# sapflux_base_v2_2.net
KiCad netlist of a schematic drawn in EAGLE
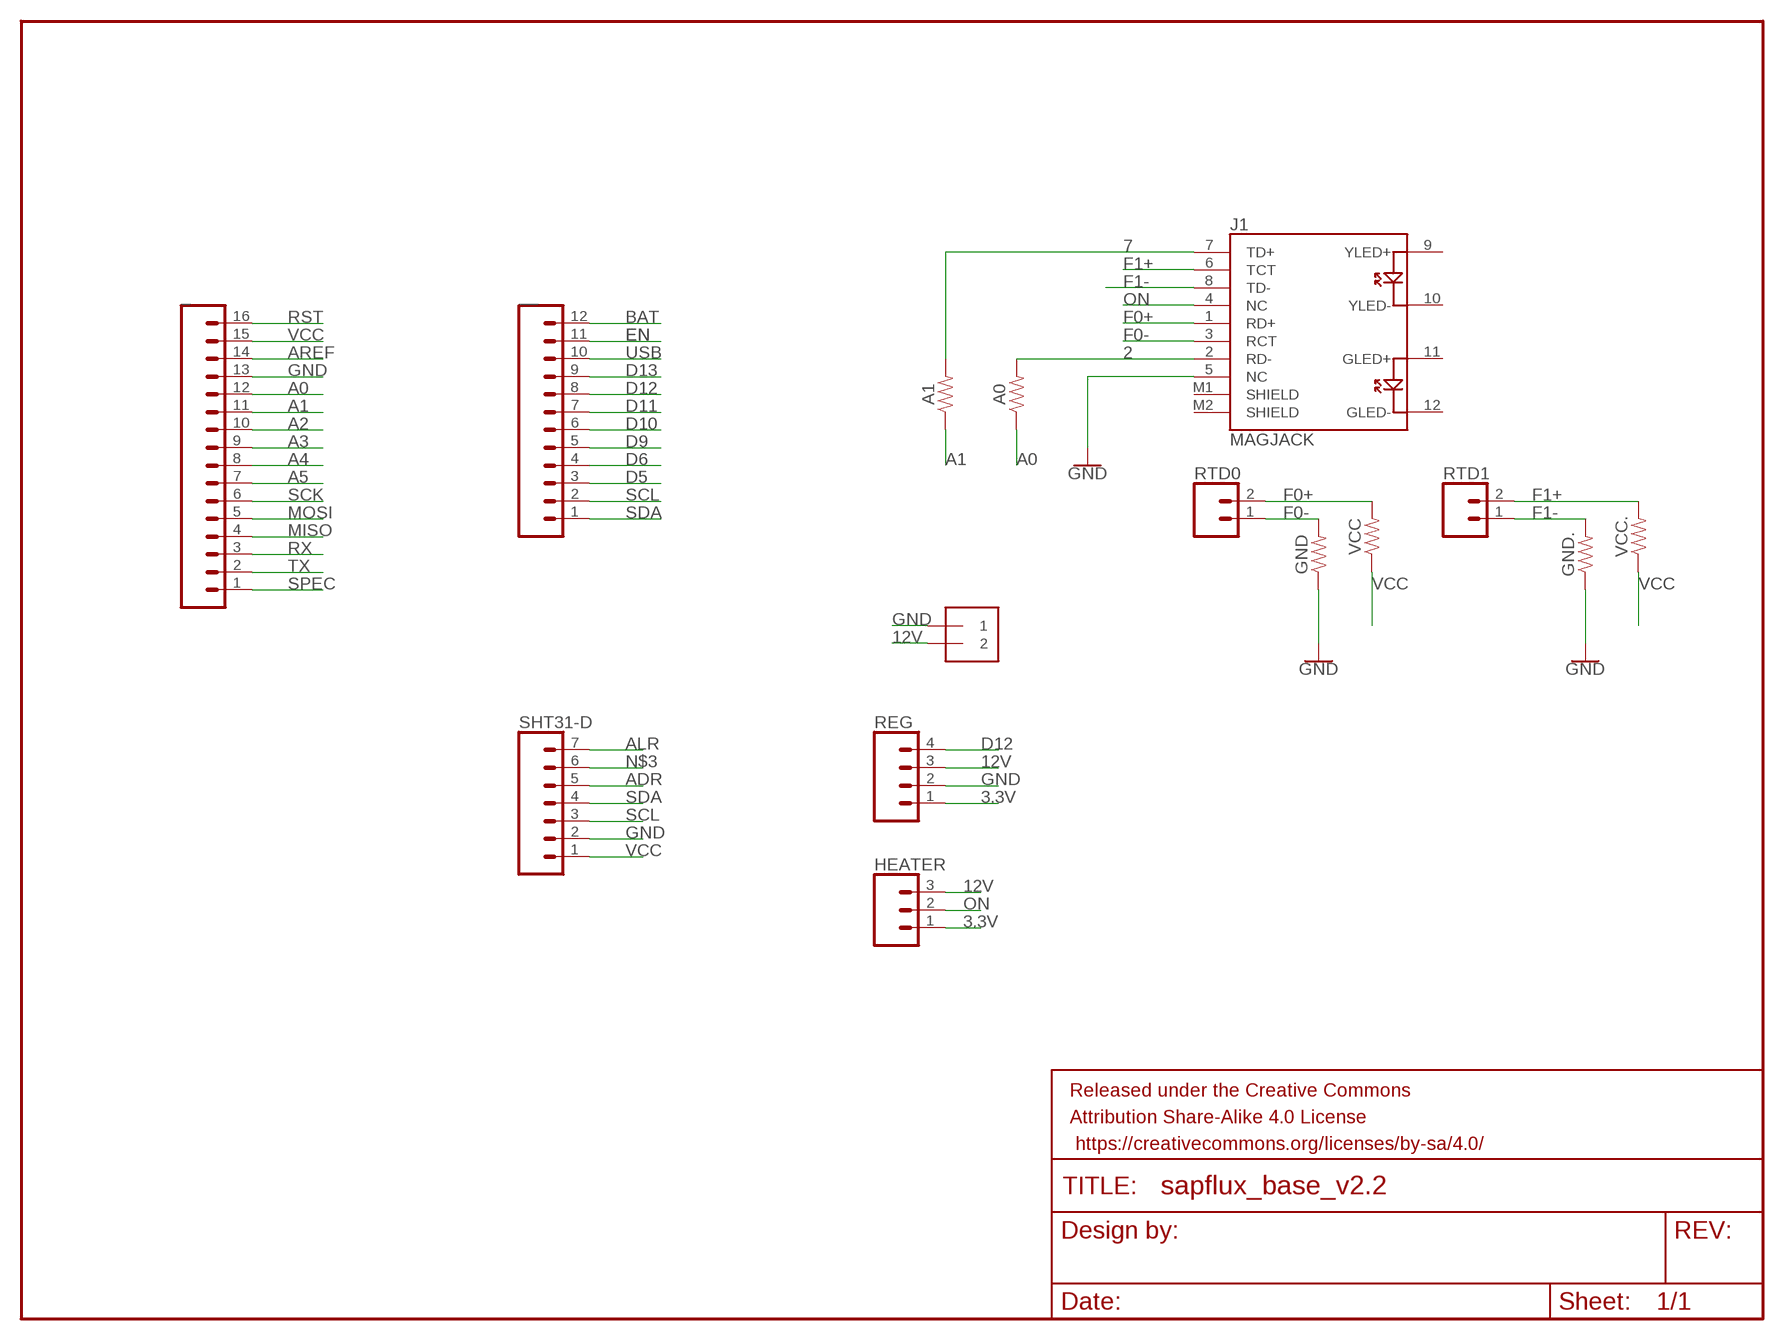
[diagram p0: schematic, sheet 1]

(export (version "E")
  (design (tool "Eeschema 10.0.6"))
  (components
    (comp (ref ".")
      (value "1X2-3.5MM")
      (footprint "eagle-import:1X2-3.5MM")
      (libsource (lib "eagle-import") (part "1X2-3.5MM"))
    )
    (comp (ref "A0")
      (value "1.8MOHM")
      (footprint "eagle-import:0603")
      (libsource (lib "eagle-import") (part "1.8MOHM"))
    )
    (comp (ref "A1")
      (value "1.8MOHM")
      (footprint "eagle-import:0603")
      (libsource (lib "eagle-import") (part "1.8MOHM"))
    )
    (comp (ref "FRAME1")
      (value "FRAME-LETTER")
      (footprint "eagle-import:CREATIVE_COMMONS")
      (libsource (lib "eagle-import") (part "FRAME-LETTER"))
    )
    (comp (ref "GND")
      (value "1.8MOHM")
      (footprint "eagle-import:0603")
      (libsource (lib "eagle-import") (part "1.8MOHM"))
    )
    (comp (ref "GND.")
      (value "1.8MOHM")
      (footprint "eagle-import:0603")
      (libsource (lib "eagle-import") (part "1.8MOHM"))
    )
    (comp (ref "HEATER")
      (value "CONN_03")
      (footprint "eagle-import:1X03")
      (libsource (lib "eagle-import") (part "CONN_03"))
    )
    (comp (ref "J1")
      (value "MAGJACK")
      (footprint "eagle-import:MAGJACK")
      (libsource (lib "eagle-import") (part "MAGJACK"))
    )
    (comp (ref "REG")
      (value "CONN_04")
      (footprint "eagle-import:1X04")
      (libsource (lib "eagle-import") (part "CONN_04"))
    )
    (comp (ref "RTD0")
      (value "CONN_02")
      (footprint "eagle-import:1X02")
      (libsource (lib "eagle-import") (part "CONN_02"))
    )
    (comp (ref "RTD1")
      (value "CONN_02")
      (footprint "eagle-import:1X02")
      (libsource (lib "eagle-import") (part "CONN_02"))
    )
    (comp (ref "SHT31-D")
      (value "CONN_07")
      (footprint "eagle-import:1X07")
      (libsource (lib "eagle-import") (part "CONN_07"))
    )
    (comp (ref "VCC")
      (value "1.8MOHM")
      (footprint "eagle-import:0603")
      (libsource (lib "eagle-import") (part "1.8MOHM"))
    )
    (comp (ref "VCC.")
      (value "1.8MOHM")
      (footprint "eagle-import:0603")
      (libsource (lib "eagle-import") (part "1.8MOHM"))
    )
    (comp (ref "_")
      (value "CONN_16")
      (footprint "eagle-import:1X16")
      (libsource (lib "eagle-import") (part "CONN_16"))
    )
    (comp (ref "__")
      (value "CONN_12")
      (footprint "eagle-import:1X12")
      (libsource (lib "eagle-import") (part "CONN_12"))
    )
  )
  (nets
    (net (code "1") (name "/2") (class "Default")
      (node (ref "A0") (pin "2") (pinfunction "2_2") (pintype "passive"))
      (node (ref "J1") (pin "2") (pinfunction "RD-_2") (pintype "bidirectional"))
    )
    (net (code "2") (name "/3.3V") (class "Default")
      (node (ref "HEATER") (pin "1") (pinfunction "1_1") (pintype "passive"))
      (node (ref "REG") (pin "1") (pinfunction "1_1") (pintype "passive"))
    )
    (net (code "3") (name "/7") (class "Default")
      (node (ref "A1") (pin "2") (pinfunction "2_2") (pintype "passive"))
      (node (ref "J1") (pin "7") (pinfunction "TD+_7") (pintype "bidirectional"))
    )
    (net (code "4") (name "/12V") (class "Default")
      (node (ref ".") (pin "2") (pinfunction "2_2") (pintype "passive"))
      (node (ref "HEATER") (pin "3") (pinfunction "3_3") (pintype "passive"))
      (node (ref "REG") (pin "3") (pinfunction "3_3") (pintype "passive"))
    )
    (net (code "5") (name "/A0") (class "Default")
      (node (ref "A0") (pin "1") (pinfunction "1_1") (pintype "passive"))
      (node (ref "_") (pin "12") (pinfunction "12_12") (pintype "passive"))
    )
    (net (code "6") (name "/A1") (class "Default")
      (node (ref "A1") (pin "1") (pinfunction "1_1") (pintype "passive"))
      (node (ref "_") (pin "11") (pinfunction "11_11") (pintype "passive"))
    )
    (net (code "7") (name "/A2") (class "Default")
      (node (ref "_") (pin "10") (pinfunction "10_10") (pintype "passive"))
    )
    (net (code "8") (name "/A3") (class "Default")
      (node (ref "_") (pin "9") (pinfunction "9_9") (pintype "passive"))
    )
    (net (code "9") (name "/A4") (class "Default")
      (node (ref "_") (pin "8") (pinfunction "8_8") (pintype "passive"))
    )
    (net (code "10") (name "/A5") (class "Default")
      (node (ref "_") (pin "7") (pinfunction "7_7") (pintype "passive"))
    )
    (net (code "11") (name "/ADR") (class "Default")
      (node (ref "SHT31-D") (pin "5") (pinfunction "5_5") (pintype "passive"))
    )
    (net (code "12") (name "/ALR") (class "Default")
      (node (ref "SHT31-D") (pin "7") (pinfunction "7_7") (pintype "passive"))
    )
    (net (code "13") (name "/AREF") (class "Default")
      (node (ref "_") (pin "14") (pinfunction "14_14") (pintype "passive"))
    )
    (net (code "14") (name "/BAT") (class "Default")
      (node (ref "__") (pin "12") (pinfunction "12_12") (pintype "passive"))
    )
    (net (code "15") (name "/D5") (class "Default")
      (node (ref "__") (pin "3") (pinfunction "3_3") (pintype "passive"))
    )
    (net (code "16") (name "/D6") (class "Default")
      (node (ref "__") (pin "4") (pinfunction "4_4") (pintype "passive"))
    )
    (net (code "17") (name "/D9") (class "Default")
      (node (ref "__") (pin "5") (pinfunction "5_5") (pintype "passive"))
    )
    (net (code "18") (name "/D10") (class "Default")
      (node (ref "__") (pin "6") (pinfunction "6_6") (pintype "passive"))
    )
    (net (code "19") (name "/D11") (class "Default")
      (node (ref "__") (pin "7") (pinfunction "7_7") (pintype "passive"))
    )
    (net (code "20") (name "/D12") (class "Default")
      (node (ref "REG") (pin "4") (pinfunction "4_4") (pintype "passive"))
      (node (ref "__") (pin "8") (pinfunction "8_8") (pintype "passive"))
    )
    (net (code "21") (name "/D13") (class "Default")
      (node (ref "__") (pin "9") (pinfunction "9_9") (pintype "passive"))
    )
    (net (code "22") (name "/EN") (class "Default")
      (node (ref "__") (pin "11") (pinfunction "11_11") (pintype "passive"))
    )
    (net (code "23") (name "/F0+") (class "Default")
      (node (ref "J1") (pin "1") (pinfunction "RD+_1") (pintype "bidirectional"))
      (node (ref "RTD0") (pin "2") (pinfunction "2_2") (pintype "passive"))
      (node (ref "VCC") (pin "2") (pinfunction "2_2") (pintype "passive"))
    )
    (net (code "24") (name "/F0-") (class "Default")
      (node (ref "GND") (pin "2") (pinfunction "2_2") (pintype "passive"))
      (node (ref "J1") (pin "3") (pinfunction "RCT_3") (pintype "bidirectional"))
      (node (ref "RTD0") (pin "1") (pinfunction "1_1") (pintype "passive"))
    )
    (net (code "25") (name "/F1+") (class "Default")
      (node (ref "J1") (pin "6") (pinfunction "TCT_6") (pintype "bidirectional"))
      (node (ref "RTD1") (pin "2") (pinfunction "2_2") (pintype "passive"))
      (node (ref "VCC.") (pin "2") (pinfunction "2_2") (pintype "passive"))
    )
    (net (code "26") (name "/F1-") (class "Default")
      (node (ref "GND.") (pin "2") (pinfunction "2_2") (pintype "passive"))
      (node (ref "J1") (pin "8") (pinfunction "TD-_8") (pintype "bidirectional"))
      (node (ref "RTD1") (pin "1") (pinfunction "1_1") (pintype "passive"))
    )
    (net (code "27") (name "/MISO") (class "Default")
      (node (ref "_") (pin "4") (pinfunction "4_4") (pintype "passive"))
    )
    (net (code "28") (name "/MOSI") (class "Default")
      (node (ref "_") (pin "5") (pinfunction "5_5") (pintype "passive"))
    )
    (net (code "29") (name "/N$3") (class "Default")
      (node (ref "SHT31-D") (pin "6") (pinfunction "6_6") (pintype "passive"))
    )
    (net (code "30") (name "/ON") (class "Default")
      (node (ref "HEATER") (pin "2") (pinfunction "2_2") (pintype "passive"))
      (node (ref "J1") (pin "4") (pinfunction "NC_4") (pintype "bidirectional"))
    )
    (net (code "31") (name "/RST") (class "Default")
      (node (ref "_") (pin "16") (pinfunction "16_16") (pintype "passive"))
    )
    (net (code "32") (name "/RX") (class "Default")
      (node (ref "_") (pin "3") (pinfunction "3_3") (pintype "passive"))
    )
    (net (code "33") (name "/SCK") (class "Default")
      (node (ref "_") (pin "6") (pinfunction "6_6") (pintype "passive"))
    )
    (net (code "34") (name "/SCL") (class "Default")
      (node (ref "SHT31-D") (pin "3") (pinfunction "3_3") (pintype "passive"))
      (node (ref "__") (pin "2") (pinfunction "2_2") (pintype "passive"))
    )
    (net (code "35") (name "/SDA") (class "Default")
      (node (ref "SHT31-D") (pin "4") (pinfunction "4_4") (pintype "passive"))
      (node (ref "__") (pin "1") (pinfunction "1_1") (pintype "passive"))
    )
    (net (code "36") (name "/SPEC") (class "Default")
      (node (ref "_") (pin "1") (pinfunction "1_1") (pintype "passive"))
    )
    (net (code "37") (name "/TX") (class "Default")
      (node (ref "_") (pin "2") (pinfunction "2_2") (pintype "passive"))
    )
    (net (code "38") (name "/USB") (class "Default")
      (node (ref "__") (pin "10") (pinfunction "10_10") (pintype "passive"))
    )
    (net (code "39") (name "/VCC") (class "Default")
      (node (ref "SHT31-D") (pin "1") (pinfunction "1_1") (pintype "passive"))
      (node (ref "VCC") (pin "1") (pinfunction "1_1") (pintype "passive"))
      (node (ref "VCC.") (pin "1") (pinfunction "1_1") (pintype "passive"))
      (node (ref "_") (pin "15") (pinfunction "15_15") (pintype "passive"))
    )
    (net (code "40") (name "GND") (class "Default")
      (node (ref ".") (pin "1") (pinfunction "1_1") (pintype "passive"))
      (node (ref "GND") (pin "1") (pinfunction "1_1") (pintype "passive"))
      (node (ref "GND.") (pin "1") (pinfunction "1_1") (pintype "passive"))
      (node (ref "J1") (pin "5") (pinfunction "NC_5") (pintype "bidirectional"))
      (node (ref "REG") (pin "2") (pinfunction "2_2") (pintype "passive"))
      (node (ref "SHT31-D") (pin "2") (pinfunction "2_2") (pintype "passive"))
      (node (ref "_") (pin "13") (pinfunction "13_13") (pintype "passive"))
    )
    (net (code "41") (name "unconnected-(J1-GLED+-Pad11)") (class "Default")
      (node (ref "J1") (pin "11") (pinfunction "GLED+_11") (pintype "bidirectional"))
    )
    (net (code "42") (name "unconnected-(J1-GLED--Pad12)") (class "Default")
      (node (ref "J1") (pin "12") (pinfunction "GLED-_12") (pintype "bidirectional"))
    )
    (net (code "43") (name "unconnected-(J1-SHIELD-PadM1)") (class "Default")
      (node (ref "J1") (pin "M1") (pinfunction "SHIELD_M1") (pintype "bidirectional"))
    )
    (net (code "44") (name "unconnected-(J1-SHIELD-PadM2)") (class "Default")
      (node (ref "J1") (pin "M2") (pinfunction "SHIELD_M2") (pintype "bidirectional"))
    )
    (net (code "45") (name "unconnected-(J1-YLED+-Pad9)") (class "Default")
      (node (ref "J1") (pin "9") (pinfunction "YLED+_9") (pintype "bidirectional"))
    )
    (net (code "46") (name "unconnected-(J1-YLED--Pad10)") (class "Default")
      (node (ref "J1") (pin "10") (pinfunction "YLED-_10") (pintype "bidirectional"))
    )
  )
)
